# H23R30.net
KiCad netlist of a schematic drawn in EAGLE
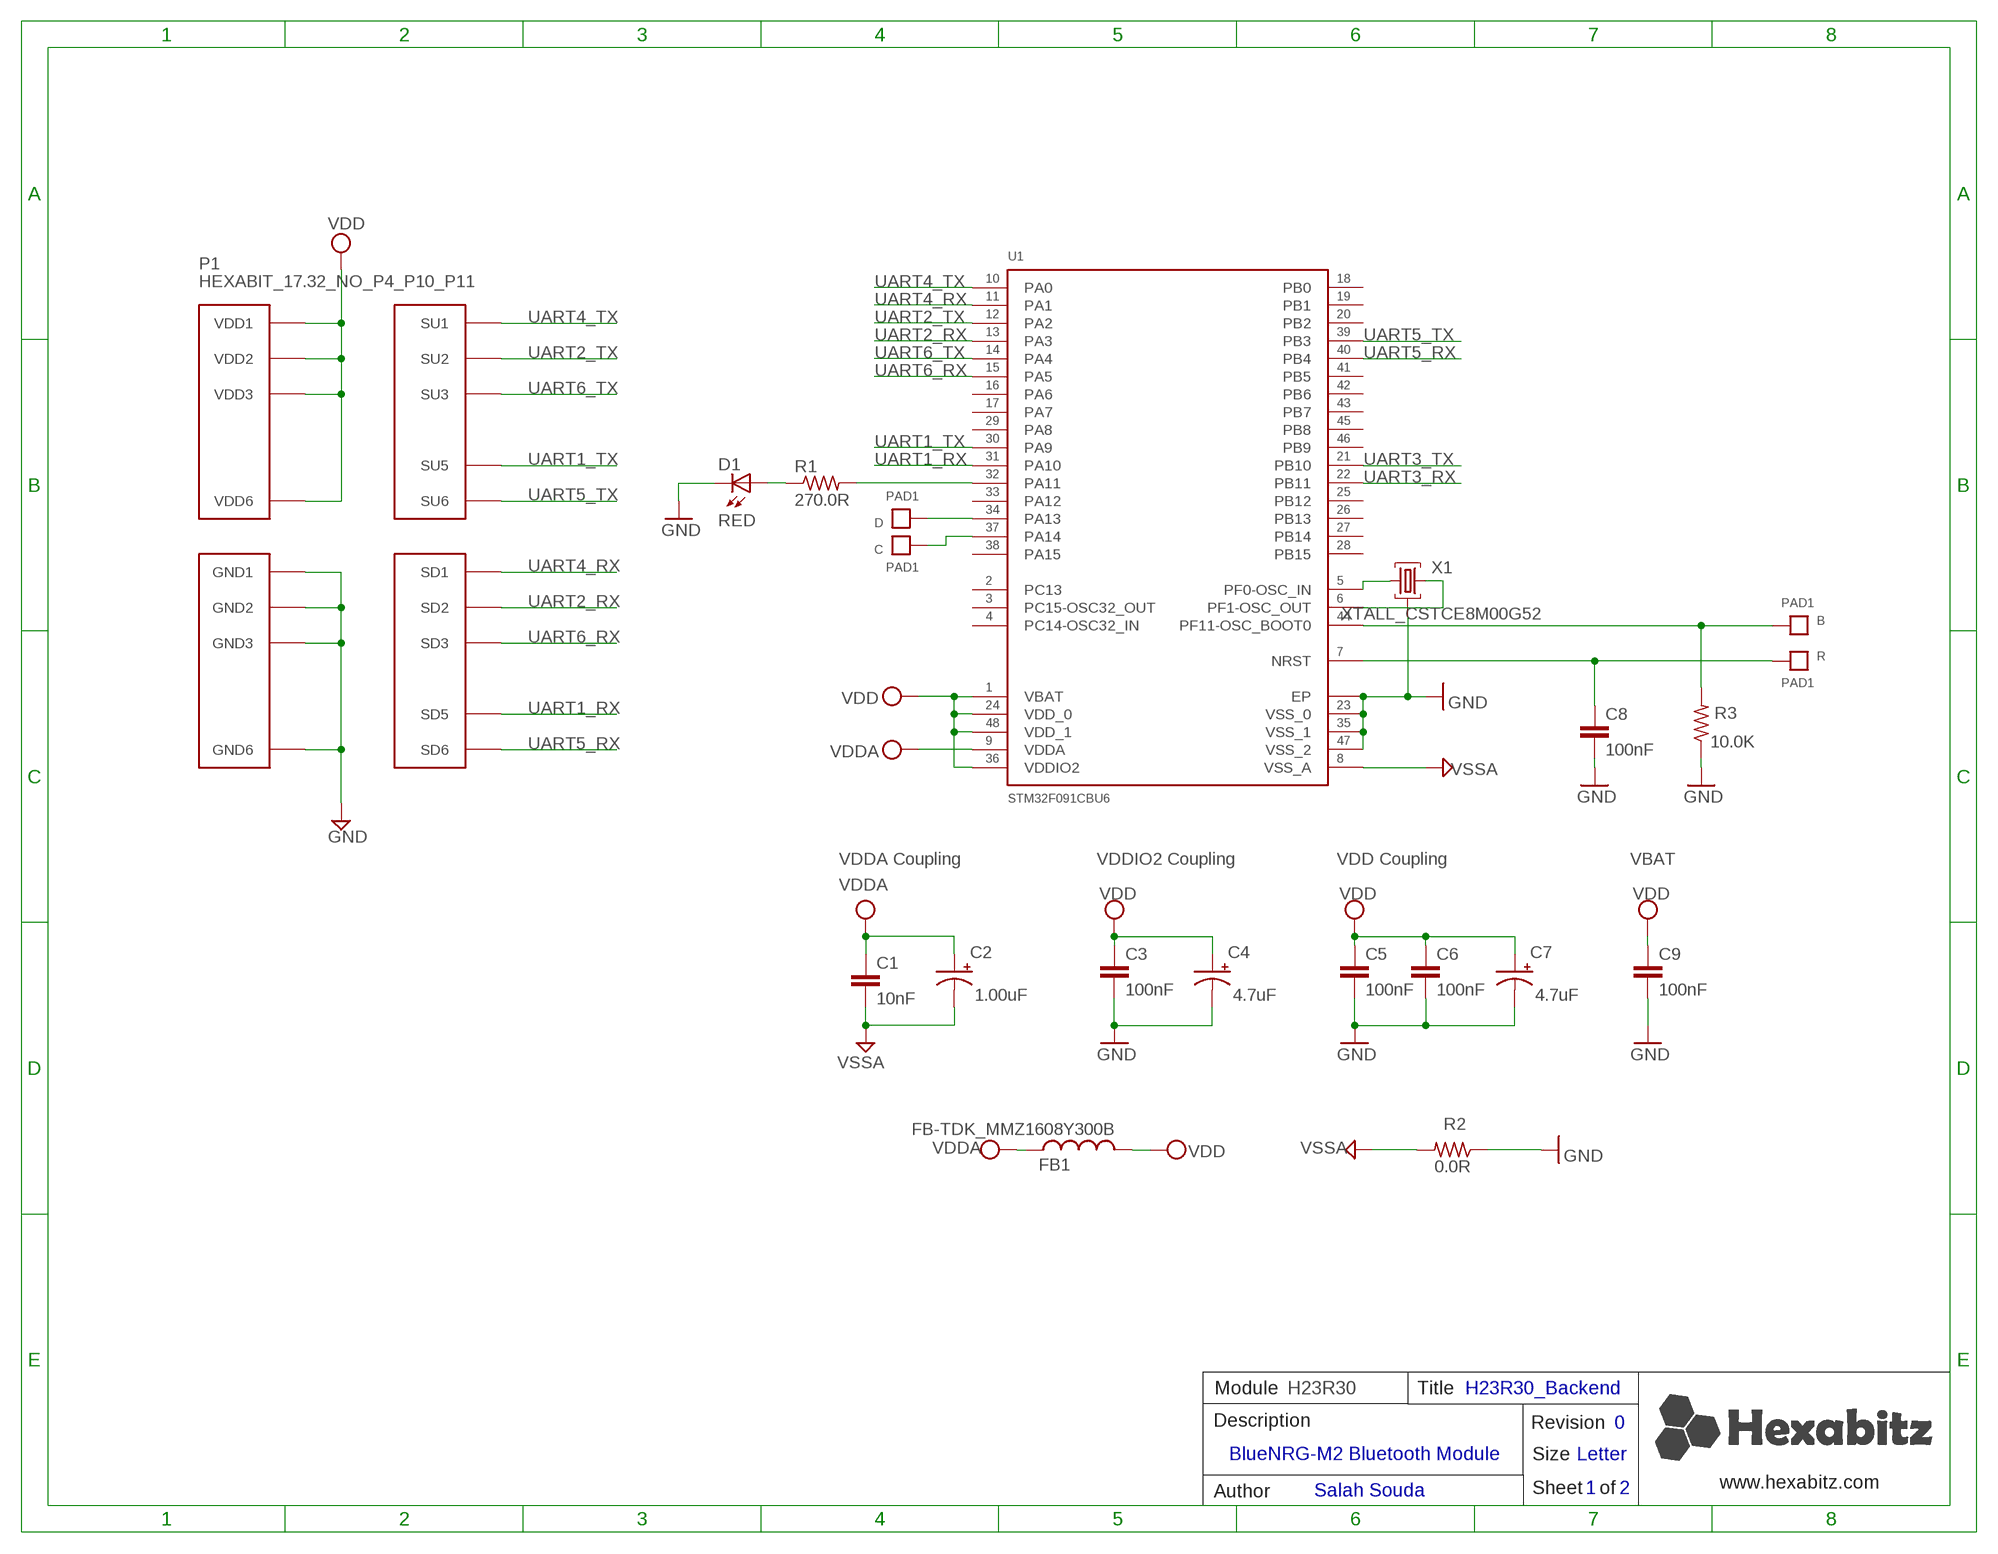
[diagram p0: schematic, sheet 1]
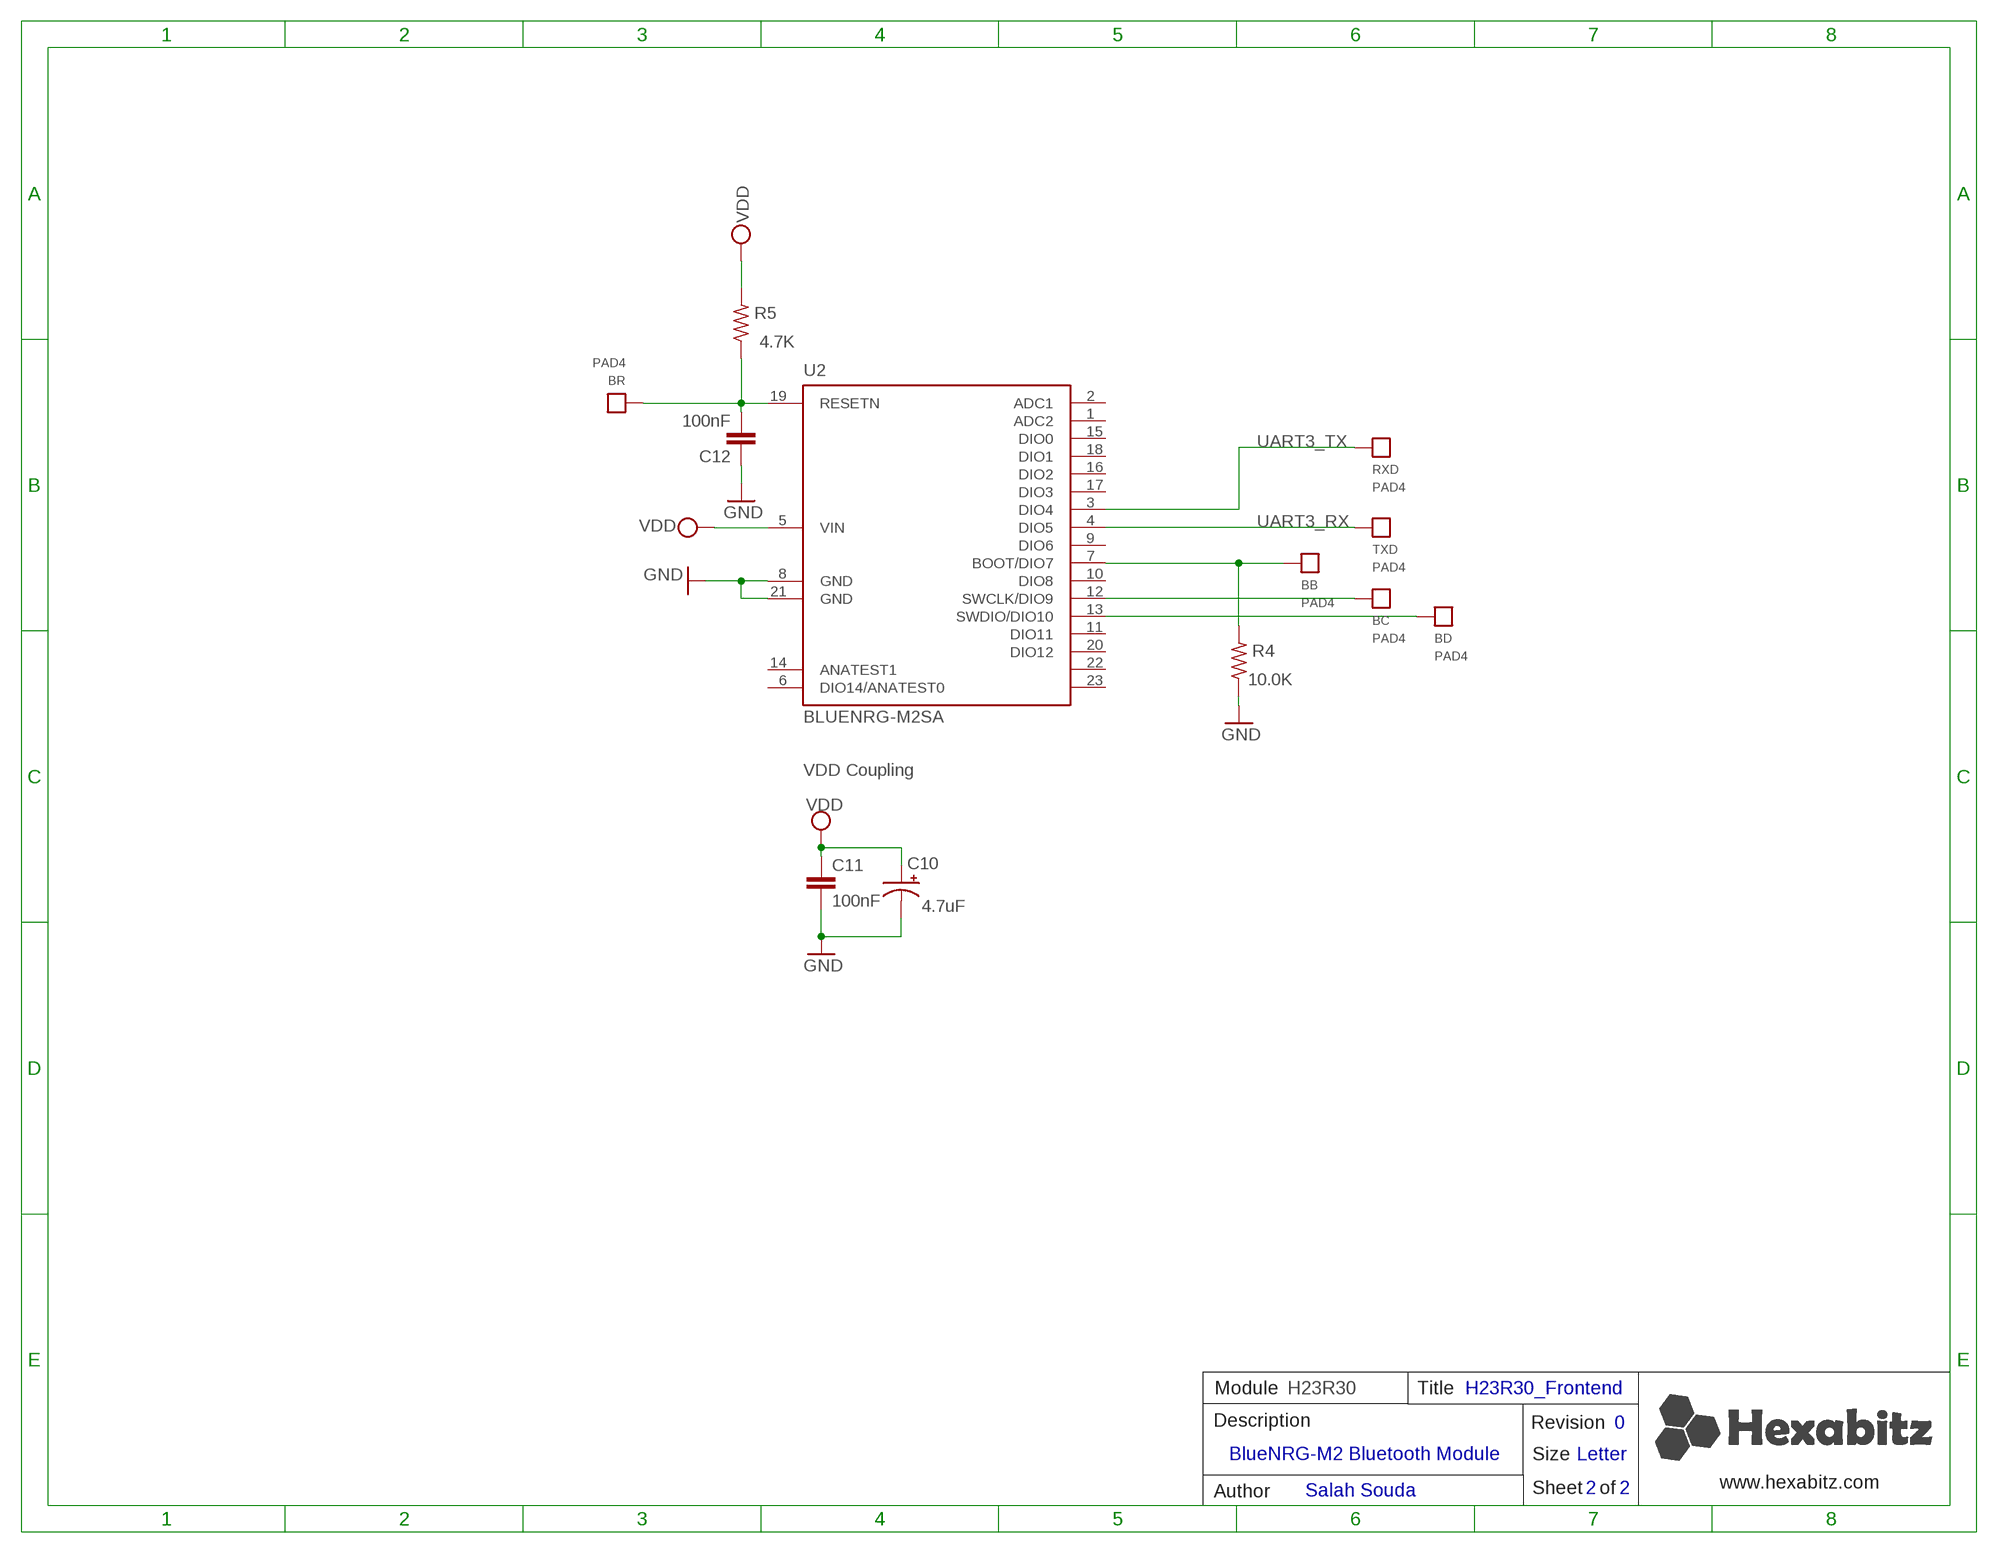
[diagram p1: schematic, sheet 2]

(export (version "E")
  (design (tool "Eeschema 10.0.6"))
  (components
    (comp (ref "B")
      (value "PAD1")
      (footprint "eagle-import:PAD1")
      (libsource (lib "eagle-import") (part "PAD1"))
    )
    (comp (ref "C")
      (value "PAD1")
      (footprint "eagle-import:PAD1")
      (libsource (lib "eagle-import") (part "PAD1"))
    )
    (comp (ref "C1")
      (value "10nF")
      (footprint "eagle-import:C-0603")
      (fields
        (field (name "CAPACITANCE") "10nF")
        (field (name "MFN") "KEMET")
        (field (name "MPN") "C0603C103K5RACTU")
        (field (name "OCTOPART_URL") "https://octopart.com/c0603c103k5ractu-kemet-133094?r=sp&s=R_iPBxLnSmGqhkU2rIMFpg")
        (field (name "TOLERANCE") "10%")
        (field (name "VOLTAGE_RATING") "50V")
      )
      (libsource (lib "eagle-import") (part "C-0603"))
    )
    (comp (ref "C2")
      (value "1.00uF")
      (footprint "eagle-import:C-0805-POL")
      (fields
        (field (name "CAPACITANCE") "1.00uF")
        (field (name "MFN") "Yageo")
        (field (name "MPN") "CC0805KKX7R7BB105")
        (field (name "OCTOPART_URL") "https://octopart.com/cc0805kkx7r7bb105-yageo-8376555?r=sp&s=YKl1wwtkROau_X5nniH2ig")
        (field (name "TOLERANCE") "10%")
        (field (name "VOLTAGE_RATING") "16V")
      )
      (libsource (lib "eagle-import") (part "C-0805-POL"))
    )
    (comp (ref "C3")
      (value "100nF")
      (footprint "eagle-import:C-0603")
      (fields
        (field (name "CAPACITANCE") "100nF")
        (field (name "MFN") "KEMET")
        (field (name "MPN") "C0603C104K8RACTU")
        (field (name "OCTOPART_URL") "https://octopart.com/c0603c104k8ractu-kemet-145075?r=sp&s=9bS9ASSwSEqMCE9KBEQZ0g")
        (field (name "TOLERANCE") "10%")
        (field (name "VOLTAGE_RATING") "10V")
      )
      (libsource (lib "eagle-import") (part "C-0603"))
    )
    (comp (ref "C4")
      (value "4.7uF")
      (footprint "eagle-import:C-0805-POL")
      (fields
        (field (name "CAPACITANCE") "4.7uF")
        (field (name "MFN") "Murata")
        (field (name "MPN") "GRM21BC81E475KA12L")
        (field (name "OCTOPART_URL") "https://octopart.com/grm21bc81e475ka12l-murata-10331911?r=sp&s=RY3qZSD8T6mG6TC9CHI5qQ")
        (field (name "TOLERANCE") "10%")
        (field (name "VOLTAGE_RATING") "25V")
      )
      (libsource (lib "eagle-import") (part "C-0805-POL"))
    )
    (comp (ref "C5")
      (value "100nF")
      (footprint "eagle-import:C-0603")
      (fields
        (field (name "CAPACITANCE") "100nF")
        (field (name "MFN") "KEMET")
        (field (name "MPN") "C0603C104K8RACTU")
        (field (name "OCTOPART_URL") "https://octopart.com/c0603c104k8ractu-kemet-145075?r=sp&s=9bS9ASSwSEqMCE9KBEQZ0g")
        (field (name "TOLERANCE") "10%")
        (field (name "VOLTAGE_RATING") "10")
      )
      (libsource (lib "eagle-import") (part "C-0603"))
    )
    (comp (ref "C6")
      (value "100nF")
      (footprint "eagle-import:C-0603")
      (fields
        (field (name "CAPACITANCE") "100nF")
        (field (name "MFN") "KEMET")
        (field (name "MPN") "C0603C104K8RACTU")
        (field (name "OCTOPART_URL") "https://octopart.com/c0603c104k8ractu-kemet-145075?r=sp&s=9bS9ASSwSEqMCE9KBEQZ0g")
        (field (name "TOLERANCE") "10%")
        (field (name "VOLTAGE_RATING") "10V")
      )
      (libsource (lib "eagle-import") (part "C-0603"))
    )
    (comp (ref "C7")
      (value "4.7uF")
      (footprint "eagle-import:C-0805-POL")
      (fields
        (field (name "CAPACITANCE") "4.7uF")
        (field (name "MFN") "Murata")
        (field (name "MPN") "GRM21BC81E475KA12L")
        (field (name "OCTOPART_URL") "https://octopart.com/grm21bc81e475ka12l-murata-10331911?r=sp&s=RY3qZSD8T6mG6TC9CHI5qQ")
        (field (name "TOLERANCE") "10%")
        (field (name "VOLTAGE_RATING") "25V")
      )
      (libsource (lib "eagle-import") (part "C-0805-POL"))
    )
    (comp (ref "C8")
      (value "100nF")
      (footprint "eagle-import:C-0603")
      (fields
        (field (name "CAPACITANCE") "100nF")
        (field (name "MFN") "KEMET")
        (field (name "MPN") "C0603C104K8RACTU")
        (field (name "OCTOPART_URL") "https://octopart.com/c0603c104k8ractu-kemet-145075?r=sp&s=9bS9ASSwSEqMCE9KBEQZ0g")
        (field (name "TOLERANCE") "10%")
        (field (name "VOLTAGE_RATING") "10V")
      )
      (libsource (lib "eagle-import") (part "C-0603"))
    )
    (comp (ref "C9")
      (value "100nF")
      (footprint "eagle-import:C-0603")
      (fields
        (field (name "CAPACITANCE") "100nF")
        (field (name "MFN") "KEMET")
        (field (name "MPN") "C0603C104K8RACTU")
        (field (name "OCTOPART_URL") "https://octopart.com/c0603c104k8ractu-kemet-145075?r=sp&s=9bS9ASSwSEqMCE9KBEQZ0g")
        (field (name "TOLERANCE") "10V")
        (field (name "VOLTAGE_RATING") "10%")
      )
      (libsource (lib "eagle-import") (part "C-0603"))
    )
    (comp (ref "D")
      (value "PAD1")
      (footprint "eagle-import:PAD1")
      (libsource (lib "eagle-import") (part "PAD1"))
    )
    (comp (ref "D1")
      (value "RED")
      (footprint "eagle-import:VLMS1300-GS08")
      (fields
        (field (name "MPN") "VLMS1300-GS08")
        (field (name "MFN") "Vishay")
        (field (name "MPN_1") "VLMS1300-GS08")
        (field (name "OCTOPART_URL") "https://octopart.com/vlms1300-gs08-vishay-21709201?r=sp&s=_gcP4_q8T1SC6PJQPTQ9yA")
      )
      (libsource (lib "eagle-import") (part "VLMS1300-GS08"))
    )
    (comp (ref "FB1")
      (value "FB-TDK_MMZ1608Y300B")
      (footprint "eagle-import:FB-TDK_MMZ1608Y300B")
      (fields
        (field (name "MFN") "TDK ")
        (field (name "MPN") "MMZ1608Y300B")
        (field (name "OCTOPART_URL") "https://octopart.com/mmz1608y300b-tdk-368280?r=sp&s=cd9_2ZEqQ9q9UNBuQgHAiA")
      )
      (libsource (lib "eagle-import") (part "FB-TDK_MMZ1608Y300B"))
    )
    (comp (ref "P1")
      (value "HEXABIT_17.32_NO_P4_P10_P11")
      (footprint "eagle-import:HEXABIT_17.32_NO_P4_P10_P11")
      (libsource (lib "eagle-import") (part "HEXABIT_?_NO_P4_P10_P1117.32"))
    )
    (comp (ref "R")
      (value "PAD1")
      (footprint "eagle-import:PAD1")
      (libsource (lib "eagle-import") (part "PAD1"))
    )
    (comp (ref "R1")
      (value "270.0R")
      (footprint "eagle-import:R-0603")
      (fields
        (field (name "MFN") "Yageo")
        (field (name "MPN") "RC0603FR-07270RL")
        (field (name "OCTOPART_URL") "https://octopart.com/search?q=RC0603FR-07270RL&start=0")
        (field (name "RESISTANCE") "270.0 Ohm")
        (field (name "TOLERANCE") "1%")
      )
      (libsource (lib "eagle-import") (part "R-0603"))
    )
    (comp (ref "R2")
      (value "0.0R")
      (footprint "eagle-import:R-0603")
      (fields
        (field (name "MFN") "Yageo")
        (field (name "MPN") "RC0603JR-070RL")
        (field (name "OCTOPART_URL") "https://octopart.com/rc0603jr-070rl-yageo-1241539?r=sp&s=X2NteqRjRNWrnx42Y0aliA")
        (field (name "RESISTANCE") "0.0 Ohm")
      )
      (libsource (lib "eagle-import") (part "R-0603"))
    )
    (comp (ref "R3")
      (value "10.0K")
      (footprint "eagle-import:R-0603")
      (fields
        (field (name "MFN") "Yageo")
        (field (name "MPN") "RC0603JR-0710KL")
        (field (name "OCTOPART_URL") "https://octopart.com/search?q=RC0603JR-0710KL&start=0")
        (field (name "RESISTANCE") "10.0K Ohm")
        (field (name "TOLERANCE") "5%")
      )
      (libsource (lib "eagle-import") (part "R-0603"))
    )
    (comp (ref "U1")
      (value "STM32F091CBU6")
      (footprint "eagle-import:STM32F091CBU6")
      (libsource (lib "eagle-import") (part "STM32F091CBU6"))
    )
    (comp (ref "X1")
      (value "XTALL_CSTCE8M00G52")
      (footprint "eagle-import:XTALL_CSTCE8M00G52")
      (fields (field (name "MPN") "CSTCE8M00G52Z-R0"))
      (libsource (lib "eagle-import") (part "XTALL_CSTCE8M00G52"))
    )
    (comp (ref "BB")
      (value "PAD4")
      (footprint "eagle-import:PAD4")
      (libsource (lib "eagle-import") (part "PAD4"))
    )
    (comp (ref "BC")
      (value "PAD4")
      (footprint "eagle-import:PAD4")
      (libsource (lib "eagle-import") (part "PAD4"))
    )
    (comp (ref "BD")
      (value "PAD4")
      (footprint "eagle-import:PAD4")
      (libsource (lib "eagle-import") (part "PAD4"))
    )
    (comp (ref "BR")
      (value "PAD4")
      (footprint "eagle-import:PAD4")
      (libsource (lib "eagle-import") (part "PAD4"))
    )
    (comp (ref "C10")
      (value "4.7uF")
      (footprint "eagle-import:C-0805-POL")
      (fields
        (field (name "CAPACITANCE") "4.7uF")
        (field (name "MFN") "Murata")
        (field (name "MPN") "GRM21BC81E475KA12L")
        (field (name "OCTOPART_URL") "https://octopart.com/grm21bc81e475ka12l-murata-10331911?r=sp&s=RY3qZSD8T6mG6TC9CHI5qQ")
        (field (name "TOLERANCE") "10%")
        (field (name "VOLTAGE_RATING") "25V")
      )
      (libsource (lib "eagle-import") (part "C-0805-POL"))
    )
    (comp (ref "C11")
      (value "100nF")
      (footprint "eagle-import:C-0603")
      (fields
        (field (name "CAPACITANCE") "100nF")
        (field (name "MFN") "KEMET")
        (field (name "MPN") "C0603C104K8RACTU")
        (field (name "OCTOPART_URL") "https://octopart.com/c0603c104k8ractu-kemet-145075?r=sp&s=9bS9ASSwSEqMCE9KBEQZ0g")
        (field (name "TOLERANCE") "10%")
        (field (name "VOLTAGE_RATING") "10")
      )
      (libsource (lib "eagle-import") (part "C-0603"))
    )
    (comp (ref "C12")
      (value "100nF")
      (footprint "eagle-import:C-0603")
      (fields
        (field (name "CAPACITANCE") "100nF")
        (field (name "MFN") "KEMET")
        (field (name "MPN") "C0603C104K8RACTU")
        (field (name "OCTOPART_URL") "https://octopart.com/c0603c104k8ractu-kemet-145075?r=sp&s=9bS9ASSwSEqMCE9KBEQZ0g")
        (field (name "TOLERANCE") "10%")
        (field (name "VOLTAGE_RATING") "10")
      )
      (libsource (lib "eagle-import") (part "C-0603"))
    )
    (comp (ref "R4")
      (value "10.0K")
      (footprint "eagle-import:R-0603")
      (fields
        (field (name "MFN") "Yageo")
        (field (name "MPN") "RC0603JR-0710KL")
        (field (name "OCTOPART_URL") "https://octopart.com/search?q=RC0603JR-0710KL&start=0")
        (field (name "RESISTANCE") "10.0K Ohm")
        (field (name "TOLERANCE") "5%")
      )
      (libsource (lib "eagle-import") (part "R-0603"))
    )
    (comp (ref "R5")
      (value "4.7K")
      (footprint "eagle-import:R-0603")
      (fields
        (field (name "MFN") "Yageo")
        (field (name "MPN") "RC0603JR-074K7L")
        (field (name "OCTOPART_URL") "https://octopart.com/rc0603jr-074k7l-yageo-55458509?r=sp")
        (field (name "RESISTANCE") "4.7K Ohm")
        (field (name "TOLERANCE") "5%")
      )
      (libsource (lib "eagle-import") (part "R-0603"))
    )
    (comp (ref "RXD")
      (value "PAD4")
      (footprint "eagle-import:PAD4")
      (libsource (lib "eagle-import") (part "PAD4"))
    )
    (comp (ref "TXD")
      (value "PAD4")
      (footprint "eagle-import:PAD4")
      (libsource (lib "eagle-import") (part "PAD4"))
    )
    (comp (ref "U2")
      (value "BLUENRG-M2SA")
      (footprint "eagle-import:BLURNGR-M2SA_FOOTPRINT")
      (fields (field (name "MPN") "BlueNRG_M2SA"))
      (libsource (lib "eagle-import") (part "BLUENRG-M2SA"))
    )
  )
  (nets
    (net (code "1") (name "GND") (class "Default")
      (node (ref "C10") (pin "2") (pinfunction "-_2") (pintype "passive"))
      (node (ref "C11") (pin "2") (pinfunction "2_2") (pintype "passive"))
      (node (ref "C12") (pin "1") (pinfunction "1_1") (pintype "passive"))
      (node (ref "C3") (pin "2") (pinfunction "2_2") (pintype "passive"))
      (node (ref "C4") (pin "2") (pinfunction "-_2") (pintype "passive"))
      (node (ref "C5") (pin "2") (pinfunction "2_2") (pintype "passive"))
      (node (ref "C6") (pin "2") (pinfunction "2_2") (pintype "passive"))
      (node (ref "C7") (pin "2") (pinfunction "-_2") (pintype "passive"))
      (node (ref "C8") (pin "2") (pinfunction "2_2") (pintype "passive"))
      (node (ref "C9") (pin "2") (pinfunction "2_2") (pintype "passive"))
      (node (ref "D1") (pin "C") (pinfunction "C_C") (pintype "passive"))
      (node (ref "P1") (pin "PAD_PD12") (pinfunction "GND6_PAD_PD12") (pintype "power_in"))
      (node (ref "P1") (pin "PAD_PD7") (pinfunction "GND1_PAD_PD7") (pintype "power_in"))
      (node (ref "P1") (pin "PAD_PD8") (pinfunction "GND2_PAD_PD8") (pintype "power_in"))
      (node (ref "P1") (pin "PAD_PD9") (pinfunction "GND3_PAD_PD9") (pintype "power_in"))
      (node (ref "R2") (pin "1") (pinfunction "1_1") (pintype "passive"))
      (node (ref "R3") (pin "1") (pinfunction "1_1") (pintype "passive"))
      (node (ref "R4") (pin "1") (pinfunction "1_1") (pintype "passive"))
      (node (ref "U1") (pin "EP") (pinfunction "EP_EP") (pintype "power_in"))
      (node (ref "U1") (pin "P$23") (pinfunction "VSS_0_P$23") (pintype "power_in"))
      (node (ref "U1") (pin "P$35") (pinfunction "VSS_1_P$35") (pintype "power_in"))
      (node (ref "U1") (pin "P$47") (pinfunction "VSS_2_P$47") (pintype "power_in"))
      (node (ref "U2") (pin "21") (pinfunction "GND_21") (pintype "power_in"))
      (node (ref "U2") (pin "8") (pinfunction "GND_8") (pintype "power_in"))
      (node (ref "X1") (pin "P$2") (pinfunction "2_P$2") (pintype "passive"))
    )
    (net (code "2") (name "Net-(D1-PadA)") (class "Default")
      (node (ref "D1") (pin "A") (pinfunction "A_A") (pintype "passive"))
      (node (ref "R1") (pin "1") (pinfunction "1_1") (pintype "passive"))
    )
    (net (code "3") (name "Net-(U1-NRST)") (class "Default")
      (node (ref "C8") (pin "1") (pinfunction "1_1") (pintype "passive"))
      (node (ref "R") (pin "P$1") (pinfunction "P$1_P$1") (pintype "passive"))
      (node (ref "R") (pin "P$2") (pinfunction "P$1_P$2") (pintype "passive"))
      (node (ref "U1") (pin "P$7") (pinfunction "NRST_P$7") (pintype "passive"))
    )
    (net (code "4") (name "Net-(U1-PA11)") (class "Default")
      (node (ref "R1") (pin "2") (pinfunction "2_2") (pintype "passive"))
      (node (ref "U1") (pin "P$32") (pinfunction "PA11_P$32") (pintype "bidirectional"))
    )
    (net (code "5") (name "Net-(U1-PA13)") (class "Default")
      (node (ref "D") (pin "P$1") (pinfunction "P$1_P$1") (pintype "passive"))
      (node (ref "D") (pin "P$2") (pinfunction "P$1_P$2") (pintype "passive"))
      (node (ref "U1") (pin "P$34") (pinfunction "PA13_P$34") (pintype "bidirectional"))
    )
    (net (code "6") (name "Net-(U1-PA14)") (class "Default")
      (node (ref "C") (pin "P$1") (pinfunction "P$1_P$1") (pintype "passive"))
      (node (ref "C") (pin "P$2") (pinfunction "P$1_P$2") (pintype "passive"))
      (node (ref "U1") (pin "P$37") (pinfunction "PA14_P$37") (pintype "bidirectional"))
    )
    (net (code "7") (name "Net-(U1-PF0-OSC_IN)") (class "Default")
      (node (ref "U1") (pin "P$5") (pinfunction "PF0-OSC_IN_P$5") (pintype "bidirectional"))
      (node (ref "X1") (pin "P$1") (pinfunction "1_P$1") (pintype "passive"))
    )
    (net (code "8") (name "Net-(U1-PF1-OSC_OUT)") (class "Default")
      (node (ref "U1") (pin "P$6") (pinfunction "PF1-OSC_OUT_P$6") (pintype "bidirectional"))
      (node (ref "X1") (pin "P$3") (pinfunction "3_P$3") (pintype "passive"))
    )
    (net (code "9") (name "Net-(U1-PF11-OSC_BOOT0)") (class "Default")
      (node (ref "B") (pin "P$1") (pinfunction "P$1_P$1") (pintype "passive"))
      (node (ref "B") (pin "P$2") (pinfunction "P$1_P$2") (pintype "passive"))
      (node (ref "R3") (pin "2") (pinfunction "2_2") (pintype "passive"))
      (node (ref "U1") (pin "P$44") (pinfunction "PF11-OSC_BOOT0_P$44") (pintype "bidirectional"))
    )
    (net (code "10") (name "Net-(U2-BOOT{slash}DIO7)") (class "Default")
      (node (ref "BB") (pin "P$1") (pinfunction "P$1_P$1") (pintype "passive"))
      (node (ref "R4") (pin "2") (pinfunction "2_2") (pintype "passive"))
      (node (ref "U2") (pin "7") (pinfunction "BOOT/DIO7_7") (pintype "bidirectional"))
    )
    (net (code "11") (name "Net-(U2-RESETN)") (class "Default")
      (node (ref "BR") (pin "P$1") (pinfunction "P$1_P$1") (pintype "passive"))
      (node (ref "C12") (pin "2") (pinfunction "2_2") (pintype "passive"))
      (node (ref "R5") (pin "1") (pinfunction "1_1") (pintype "passive"))
      (node (ref "U2") (pin "19") (pinfunction "RESETN_19") (pintype "input"))
    )
    (net (code "12") (name "Net-(U2-SWCLK{slash}DIO9)") (class "Default")
      (node (ref "BC") (pin "P$1") (pinfunction "P$1_P$1") (pintype "passive"))
      (node (ref "U2") (pin "12") (pinfunction "SWCLK/DIO9_12") (pintype "bidirectional"))
    )
    (net (code "13") (name "Net-(U2-SWDIO{slash}DIO10)") (class "Default")
      (node (ref "BD") (pin "P$1") (pinfunction "P$1_P$1") (pintype "passive"))
      (node (ref "U2") (pin "13") (pinfunction "SWDIO/DIO10_13") (pintype "bidirectional"))
    )
    (net (code "14") (name "UART1_RX") (class "Default")
      (node (ref "P1") (pin "PAD_PD5") (pinfunction "SD5_PAD_PD5") (pintype "bidirectional"))
      (node (ref "U1") (pin "P$31") (pinfunction "PA10_P$31") (pintype "bidirectional"))
    )
    (net (code "15") (name "UART1_TX") (class "Default")
      (node (ref "P1") (pin "PAD_PU5") (pinfunction "SU5_PAD_PU5") (pintype "bidirectional"))
      (node (ref "U1") (pin "P$30") (pinfunction "PA9_P$30") (pintype "bidirectional"))
    )
    (net (code "16") (name "UART2_RX") (class "Default")
      (node (ref "P1") (pin "PAD_PD2") (pinfunction "SD2_PAD_PD2") (pintype "bidirectional"))
      (node (ref "U1") (pin "P$13") (pinfunction "PA3_P$13") (pintype "bidirectional"))
    )
    (net (code "17") (name "UART2_TX") (class "Default")
      (node (ref "P1") (pin "PAD_PU2") (pinfunction "SU2_PAD_PU2") (pintype "bidirectional"))
      (node (ref "U1") (pin "P$12") (pinfunction "PA2_P$12") (pintype "bidirectional"))
    )
    (net (code "18") (name "UART3_RX") (class "Default")
      (node (ref "TXD") (pin "P$1") (pinfunction "P$1_P$1") (pintype "passive"))
      (node (ref "U1") (pin "P$22") (pinfunction "PB11_P$22") (pintype "bidirectional"))
      (node (ref "U2") (pin "4") (pinfunction "DIO5_4") (pintype "bidirectional"))
    )
    (net (code "19") (name "UART3_TX") (class "Default")
      (node (ref "RXD") (pin "P$1") (pinfunction "P$1_P$1") (pintype "passive"))
      (node (ref "U1") (pin "P$21") (pinfunction "PB10_P$21") (pintype "bidirectional"))
      (node (ref "U2") (pin "3") (pinfunction "DIO4_3") (pintype "bidirectional"))
    )
    (net (code "20") (name "UART4_RX") (class "Default")
      (node (ref "P1") (pin "PAD_PD1") (pinfunction "SD1_PAD_PD1") (pintype "bidirectional"))
      (node (ref "U1") (pin "P$11") (pinfunction "PA1_P$11") (pintype "bidirectional"))
    )
    (net (code "21") (name "UART4_TX") (class "Default")
      (node (ref "P1") (pin "PAD_PU1") (pinfunction "SU1_PAD_PU1") (pintype "bidirectional"))
      (node (ref "U1") (pin "P$10") (pinfunction "PA0_P$10") (pintype "bidirectional"))
    )
    (net (code "22") (name "UART5_RX") (class "Default")
      (node (ref "P1") (pin "PAD_PD6") (pinfunction "SD6_PAD_PD6") (pintype "bidirectional"))
      (node (ref "U1") (pin "P$40") (pinfunction "PB4_P$40") (pintype "bidirectional"))
    )
    (net (code "23") (name "UART5_TX") (class "Default")
      (node (ref "P1") (pin "PAD_PU6") (pinfunction "SU6_PAD_PU6") (pintype "bidirectional"))
      (node (ref "U1") (pin "P$39") (pinfunction "PB3_P$39") (pintype "bidirectional"))
    )
    (net (code "24") (name "UART6_RX") (class "Default")
      (node (ref "P1") (pin "PAD_PD3") (pinfunction "SD3_PAD_PD3") (pintype "bidirectional"))
      (node (ref "U1") (pin "P$15") (pinfunction "PA5_P$15") (pintype "bidirectional"))
    )
    (net (code "25") (name "UART6_TX") (class "Default")
      (node (ref "P1") (pin "PAD_PU3") (pinfunction "SU3_PAD_PU3") (pintype "bidirectional"))
      (node (ref "U1") (pin "P$14") (pinfunction "PA4_P$14") (pintype "bidirectional"))
    )
    (net (code "26") (name "VDD") (class "Default")
      (node (ref "C10") (pin "1") (pinfunction "+_1") (pintype "passive"))
      (node (ref "C11") (pin "1") (pinfunction "1_1") (pintype "passive"))
      (node (ref "C3") (pin "1") (pinfunction "1_1") (pintype "passive"))
      (node (ref "C4") (pin "1") (pinfunction "+_1") (pintype "passive"))
      (node (ref "C5") (pin "1") (pinfunction "1_1") (pintype "passive"))
      (node (ref "C6") (pin "1") (pinfunction "1_1") (pintype "passive"))
      (node (ref "C7") (pin "1") (pinfunction "+_1") (pintype "passive"))
      (node (ref "C9") (pin "1") (pinfunction "1_1") (pintype "passive"))
      (node (ref "FB1") (pin "2") (pinfunction "2_2") (pintype "passive"))
      (node (ref "P1") (pin "PAD_PU12") (pinfunction "VDD6_PAD_PU12") (pintype "power_in"))
      (node (ref "P1") (pin "PAD_PU7") (pinfunction "VDD1_PAD_PU7") (pintype "power_in"))
      (node (ref "P1") (pin "PAD_PU8") (pinfunction "VDD2_PAD_PU8") (pintype "power_in"))
      (node (ref "P1") (pin "PAD_PU9") (pinfunction "VDD3_PAD_PU9") (pintype "power_in"))
      (node (ref "R5") (pin "2") (pinfunction "2_2") (pintype "passive"))
      (node (ref "U1") (pin "P$1") (pinfunction "VBAT_P$1") (pintype "power_in"))
      (node (ref "U1") (pin "P$24") (pinfunction "VDD_0_P$24") (pintype "power_in"))
      (node (ref "U1") (pin "P$36") (pinfunction "VDDIO2_P$36") (pintype "power_in"))
      (node (ref "U1") (pin "P$48") (pinfunction "VDD_1_P$48") (pintype "power_in"))
      (node (ref "U2") (pin "5") (pinfunction "VIN_5") (pintype "power_in"))
    )
    (net (code "27") (name "VDDA") (class "Default")
      (node (ref "C1") (pin "1") (pinfunction "1_1") (pintype "passive"))
      (node (ref "C2") (pin "1") (pinfunction "+_1") (pintype "passive"))
      (node (ref "FB1") (pin "1") (pinfunction "1_1") (pintype "passive"))
      (node (ref "U1") (pin "P$9") (pinfunction "VDDA_P$9") (pintype "power_in"))
    )
    (net (code "28") (name "VSSA") (class "Default")
      (node (ref "C1") (pin "2") (pinfunction "2_2") (pintype "passive"))
      (node (ref "C2") (pin "2") (pinfunction "-_2") (pintype "passive"))
      (node (ref "R2") (pin "2") (pinfunction "2_2") (pintype "passive"))
      (node (ref "U1") (pin "P$8") (pinfunction "VSS_A_P$8") (pintype "power_in"))
    )
    (net (code "29") (name "unconnected-(U1-PA6-PadP$16)") (class "Default")
      (node (ref "U1") (pin "P$16") (pinfunction "PA6_P$16") (pintype "bidirectional"))
    )
    (net (code "30") (name "unconnected-(U1-PA7-PadP$17)") (class "Default")
      (node (ref "U1") (pin "P$17") (pinfunction "PA7_P$17") (pintype "bidirectional"))
    )
    (net (code "31") (name "unconnected-(U1-PA8-PadP$29)") (class "Default")
      (node (ref "U1") (pin "P$29") (pinfunction "PA8_P$29") (pintype "bidirectional"))
    )
    (net (code "32") (name "unconnected-(U1-PA12-PadP$33)") (class "Default")
      (node (ref "U1") (pin "P$33") (pinfunction "PA12_P$33") (pintype "bidirectional"))
    )
    (net (code "33") (name "unconnected-(U1-PA15-PadP$38)") (class "Default")
      (node (ref "U1") (pin "P$38") (pinfunction "PA15_P$38") (pintype "bidirectional"))
    )
    (net (code "34") (name "unconnected-(U1-PB0-PadP$18)") (class "Default")
      (node (ref "U1") (pin "P$18") (pinfunction "PB0_P$18") (pintype "bidirectional"))
    )
    (net (code "35") (name "unconnected-(U1-PB1-PadP$19)") (class "Default")
      (node (ref "U1") (pin "P$19") (pinfunction "PB1_P$19") (pintype "bidirectional"))
    )
    (net (code "36") (name "unconnected-(U1-PB2-PadP$20)") (class "Default")
      (node (ref "U1") (pin "P$20") (pinfunction "PB2_P$20") (pintype "bidirectional"))
    )
    (net (code "37") (name "unconnected-(U1-PB5-PadP$41)") (class "Default")
      (node (ref "U1") (pin "P$41") (pinfunction "PB5_P$41") (pintype "bidirectional"))
    )
    (net (code "38") (name "unconnected-(U1-PB6-PadP$42)") (class "Default")
      (node (ref "U1") (pin "P$42") (pinfunction "PB6_P$42") (pintype "bidirectional"))
    )
    (net (code "39") (name "unconnected-(U1-PB7-PadP$43)") (class "Default")
      (node (ref "U1") (pin "P$43") (pinfunction "PB7_P$43") (pintype "bidirectional"))
    )
    (net (code "40") (name "unconnected-(U1-PB8-PadP$45)") (class "Default")
      (node (ref "U1") (pin "P$45") (pinfunction "PB8_P$45") (pintype "bidirectional"))
    )
    (net (code "41") (name "unconnected-(U1-PB9-PadP$46)") (class "Default")
      (node (ref "U1") (pin "P$46") (pinfunction "PB9_P$46") (pintype "bidirectional"))
    )
    (net (code "42") (name "unconnected-(U1-PB12-PadP$25)") (class "Default")
      (node (ref "U1") (pin "P$25") (pinfunction "PB12_P$25") (pintype "bidirectional"))
    )
    (net (code "43") (name "unconnected-(U1-PB13-PadP$26)") (class "Default")
      (node (ref "U1") (pin "P$26") (pinfunction "PB13_P$26") (pintype "bidirectional"))
    )
    (net (code "44") (name "unconnected-(U1-PB14-PadP$27)") (class "Default")
      (node (ref "U1") (pin "P$27") (pinfunction "PB14_P$27") (pintype "bidirectional"))
    )
    (net (code "45") (name "unconnected-(U1-PB15-PadP$28)") (class "Default")
      (node (ref "U1") (pin "P$28") (pinfunction "PB15_P$28") (pintype "bidirectional"))
    )
    (net (code "46") (name "unconnected-(U1-PC13-PadP$2)") (class "Default")
      (node (ref "U1") (pin "P$2") (pinfunction "PC13_P$2") (pintype "bidirectional"))
    )
    (net (code "47") (name "unconnected-(U1-PC14-OSC32_IN-PadP$3)") (class "Default")
      (node (ref "U1") (pin "P$3") (pinfunction "PC14-OSC32_IN_P$3") (pintype "bidirectional"))
    )
    (net (code "48") (name "unconnected-(U1-PC15-OSC32_OUT-PadP$4)") (class "Default")
      (node (ref "U1") (pin "P$4") (pinfunction "PC15-OSC32_OUT_P$4") (pintype "bidirectional"))
    )
    (net (code "49") (name "unconnected-(U2-ADC1-Pad2)") (class "Default")
      (node (ref "U2") (pin "2") (pinfunction "ADC1_2") (pintype "input"))
    )
    (net (code "50") (name "unconnected-(U2-ADC2-Pad1)") (class "Default")
      (node (ref "U2") (pin "1") (pinfunction "ADC2_1") (pintype "input"))
    )
    (net (code "51") (name "unconnected-(U2-ANATEST1-Pad14)") (class "Default")
      (node (ref "U2") (pin "14") (pinfunction "ANATEST1_14") (pintype "bidirectional"))
    )
    (net (code "52") (name "unconnected-(U2-DIO0-Pad15)") (class "Default")
      (node (ref "U2") (pin "15") (pinfunction "DIO0_15") (pintype "bidirectional"))
    )
    (net (code "53") (name "unconnected-(U2-DIO1-Pad18)") (class "Default")
      (node (ref "U2") (pin "18") (pinfunction "DIO1_18") (pintype "bidirectional"))
    )
    (net (code "54") (name "unconnected-(U2-DIO2-Pad16)") (class "Default")
      (node (ref "U2") (pin "16") (pinfunction "DIO2_16") (pintype "bidirectional"))
    )
    (net (code "55") (name "unconnected-(U2-DIO3-Pad17)") (class "Default")
      (node (ref "U2") (pin "17") (pinfunction "DIO3_17") (pintype "bidirectional"))
    )
    (net (code "56") (name "unconnected-(U2-DIO6-Pad9)") (class "Default")
      (node (ref "U2") (pin "9") (pinfunction "DIO6_9") (pintype "bidirectional"))
    )
    (net (code "57") (name "unconnected-(U2-DIO8-Pad10)") (class "Default")
      (node (ref "U2") (pin "10") (pinfunction "DIO8_10") (pintype "bidirectional"))
    )
    (net (code "58") (name "unconnected-(U2-DIO11-Pad11)") (class "Default")
      (node (ref "U2") (pin "11") (pinfunction "DIO11_11") (pintype "bidirectional"))
    )
    (net (code "59") (name "unconnected-(U2-DIO12-Pad20)") (class "Default")
      (node (ref "U2") (pin "20") (pinfunction "DIO12_20") (pintype "input"))
    )
    (net (code "60") (name "unconnected-(U2-DIO14{slash}ANATEST0-Pad6)") (class "Default")
      (node (ref "U2") (pin "6") (pinfunction "DIO14/ANATEST0_6") (pintype "bidirectional"))
    )
    (net (code "61") (name "unconnected-(U2-P$22-Pad22)") (class "Default")
      (node (ref "U2") (pin "22") (pinfunction "P$22_22") (pintype "no_connect"))
    )
    (net (code "62") (name "unconnected-(U2-P$23-Pad23)") (class "Default")
      (node (ref "U2") (pin "23") (pinfunction "P$23_23") (pintype "no_connect"))
    )
  )
)
